# PDB_Custom_MCU.net
KiCad netlist of a schematic drawn in Altium Designer
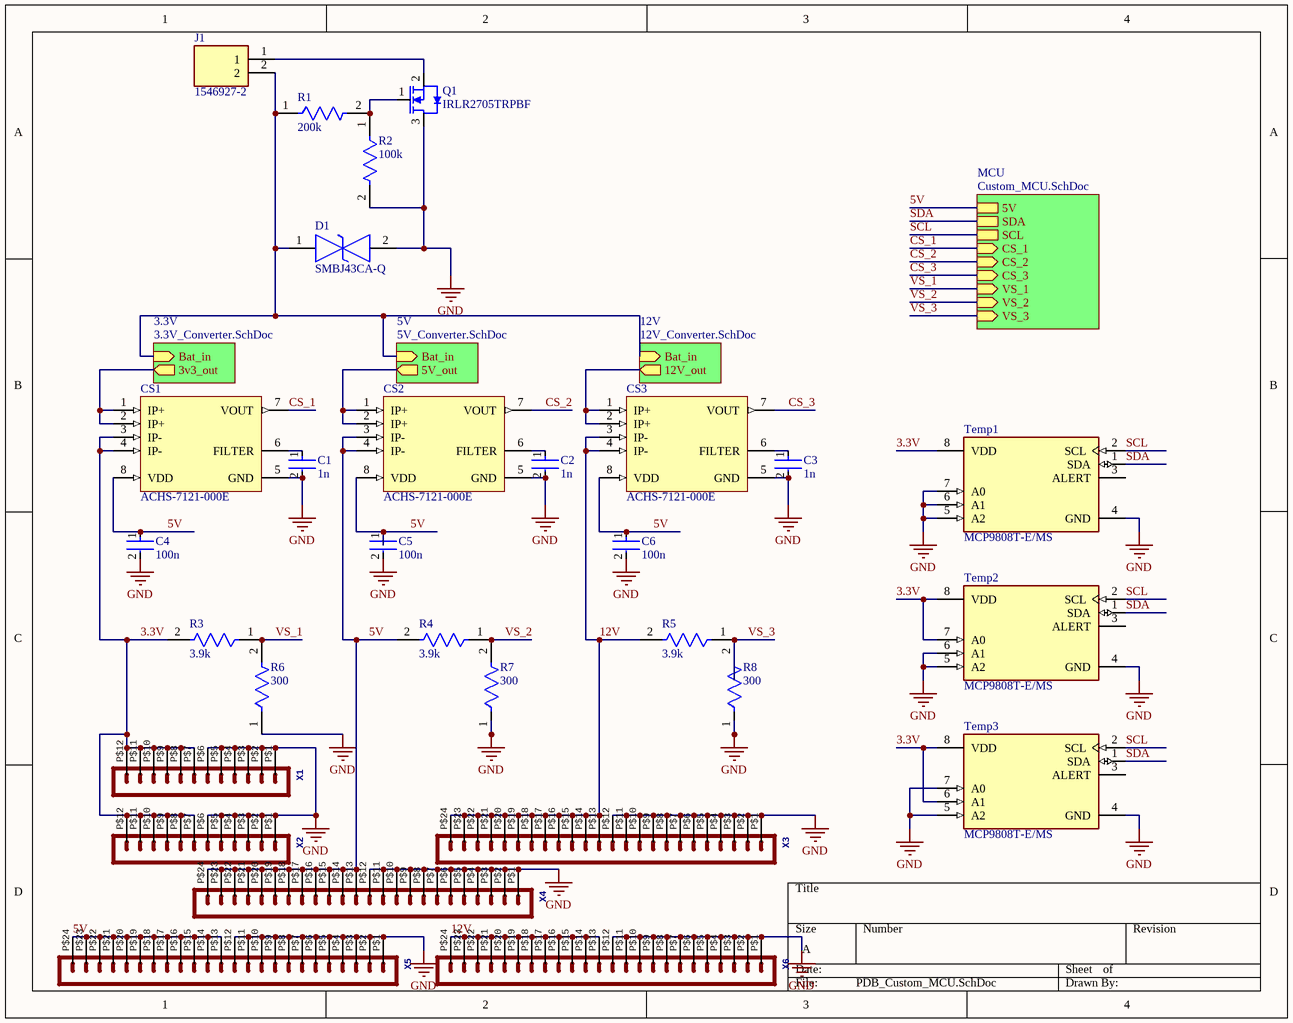
[diagram p0: PDB_Custom_MCU.SchDoc]

(export (version "E")
  (design (tool "Eeschema 10.0.6"))
  (components
    (comp (ref "C1")
      (value "1n")
      (footprint "FP-0603-L_1_6_0_15-W_0_81-IPC_A")
      (description "General Purpose Ceramic Capacitor, 0603, 1nF, 10%, X7R, 15%, 50V")
      (fields (field (name "VOLTAGE") "50V") (field (name "TOLERANCE") "10%"))
      (libsource (lib "Altium Content Vault") (part "02cd4be3c70576c341d710602a673aa"))
    )
    (comp (ref "C2")
      (value "1n")
      (footprint "FP-0603-L_1_6_0_15-W_0_81-IPC_A")
      (description "General Purpose Ceramic Capacitor, 0603, 1nF, 10%, X7R, 15%, 50V")
      (fields (field (name "VOLTAGE") "50V") (field (name "TOLERANCE") "10%"))
      (libsource (lib "Altium Content Vault") (part "02cd4be3c70576c341d710602a673aa"))
    )
    (comp (ref "C3")
      (value "1n")
      (footprint "FP-0603-L_1_6_0_15-W_0_81-IPC_A")
      (description "General Purpose Ceramic Capacitor, 0603, 1nF, 10%, X7R, 15%, 50V")
      (fields (field (name "VOLTAGE") "50V") (field (name "TOLERANCE") "10%"))
      (libsource (lib "Altium Content Vault") (part "02cd4be3c70576c341d710602a673aa"))
    )
    (comp (ref "C4")
      (value "100n")
      (footprint "FP-CGA3E-0_3-0_1-IPC_A")
      (description "Cap Ceramic 100nF 50V X7R 10% Pad SMD 0603 +125°C Automotive T/R")
      (fields (field (name "TOLERANCE") "10%") (field (name "VOLTAGE") "50V"))
      (libsource (lib "Altium Content Vault") (part "b4654b650e69147ec39a6b967a45e02"))
    )
    (comp (ref "C5")
      (value "100n")
      (footprint "FP-CGA3E-0_3-0_1-IPC_A")
      (description "Cap Ceramic 100nF 50V X7R 10% Pad SMD 0603 +125°C Automotive T/R")
      (fields (field (name "TOLERANCE") "10%") (field (name "VOLTAGE") "50V"))
      (libsource (lib "Altium Content Vault") (part "b4654b650e69147ec39a6b967a45e02"))
    )
    (comp (ref "C6")
      (value "100n")
      (footprint "FP-CGA3E-0_3-0_1-IPC_A")
      (description "Cap Ceramic 100nF 50V X7R 10% Pad SMD 0603 +125°C Automotive T/R")
      (fields (field (name "TOLERANCE") "10%") (field (name "VOLTAGE") "50V"))
      (libsource (lib "Altium Content Vault") (part "b4654b650e69147ec39a6b967a45e02"))
    )
    (comp (ref "CS1")
      (value "ACHS-7121-000E")
      (footprint "ACHS-7121-000E")
      (libsource (lib "ACHS-7121-000ECurrentSensor") (part "ACHS-7121-000E"))
    )
    (comp (ref "CS2")
      (value "ACHS-7121-000E")
      (footprint "ACHS-7121-000E")
      (libsource (lib "ACHS-7121-000ECurrentSensor") (part "ACHS-7121-000E"))
    )
    (comp (ref "CS3")
      (value "ACHS-7121-000E")
      (footprint "ACHS-7121-000E")
      (libsource (lib "ACHS-7121-000ECurrentSensor") (part "ACHS-7121-000E"))
    )
    (comp (ref "D1")
      (value "SMBJ43CA-Q")
      (footprint "SamacSys:DIONM5436X244N")
      (description "TVS Diode (Bi-directional)")
      (fields
        (field (name "MOUSER PART NUMBER") "652-SMBJ43CA-Q")
        (field (name "JLCPCB PART NUMBER") "C224021")
      )
      (libsource (lib "*") (part "SMBJ43CA-Q"))
    )
    (comp (ref "J1")
      (value "1546927-2")
      (footprint "SamacSys:SHDR2W119P0X826_1X2_1770X1549X1549P")
      (description "Connector")
      (fields (field (name "MOUSER PART NUMBER") "571-1546927-2"))
      (libsource (lib "*") (part "1546927-2"))
    )
    (comp (ref "Q1")
      (value "IRLR2705TRPBF")
      (footprint "IRLR2705TRPBF")
      (libsource (lib "Mosfetlib") (part "IRLR2705TRPBF"))
    )
    (comp (ref "R1")
      (value "200k")
      (footprint "FP-CRCW0603-e3-IPC_C")
      (description "RES Thick Film, 200kΩ, 1%, 0.1W, 100ppm/°C, 0603")
      (fields (field (name "TOLERANCE") "1%"))
      (libsource (lib "Altium Content Vault") (part "1029c3af85768c4190bb7ad29bc67b5"))
    )
    (comp (ref "R2")
      (value "100k")
      (footprint "FP-RC0603-0_55-MFG")
      (description "RES SMD 100K OHM 1% 1/10W 0603")
      (fields (field (name "TOLERANCE") "1%"))
      (libsource (lib "Altium Content Vault") (part "1029c3af85768c4190bb7ad29bc67b5"))
    )
    (comp (ref "R3")
      (value "3.9k")
      (footprint "FP-CRCW0603-e3-IPC_A")
      (description "RES Thick Film, 3.9kΩ, 1%, 0.1W, 100ppm/°C, 0603")
      (fields (field (name "TOLERANCE") "1%"))
      (libsource (lib "Altium Content Vault") (part "1029c3af85768c4190bb7ad29bc67b5"))
    )
    (comp (ref "R4")
      (value "3.9k")
      (footprint "FP-CRCW0603-e3-IPC_A")
      (description "RES Thick Film, 3.9kΩ, 1%, 0.1W, 100ppm/°C, 0603")
      (fields (field (name "TOLERANCE") "1%"))
      (libsource (lib "Altium Content Vault") (part "1029c3af85768c4190bb7ad29bc67b5"))
    )
    (comp (ref "R5")
      (value "3.9k")
      (footprint "FP-CRCW0603-e3-IPC_A")
      (description "RES Thick Film, 3.9kΩ, 1%, 0.1W, 100ppm/°C, 0603")
      (fields (field (name "TOLERANCE") "1%"))
      (libsource (lib "Altium Content Vault") (part "1029c3af85768c4190bb7ad29bc67b5"))
    )
    (comp (ref "R6")
      (value "300")
      (footprint "FP-CRCW0603-e3-IPC_A")
      (description "RES Thick Film, 300Ω, 1%, 0.1W, 100ppm/°C, 0603")
      (fields (field (name "TOLERANCE") "1%"))
      (libsource (lib "Altium Content Vault") (part "1029c3af85768c4190bb7ad29bc67b5"))
    )
    (comp (ref "R7")
      (value "300")
      (footprint "FP-CRCW0603-e3-IPC_A")
      (description "RES Thick Film, 300Ω, 1%, 0.1W, 100ppm/°C, 0603")
      (fields (field (name "TOLERANCE") "1%"))
      (libsource (lib "Altium Content Vault") (part "1029c3af85768c4190bb7ad29bc67b5"))
    )
    (comp (ref "R8")
      (value "300")
      (footprint "FP-CRCW0603-e3-IPC_A")
      (description "RES Thick Film, 300Ω, 1%, 0.1W, 100ppm/°C, 0603")
      (fields (field (name "TOLERANCE") "1%"))
      (libsource (lib "Altium Content Vault") (part "1029c3af85768c4190bb7ad29bc67b5"))
    )
    (comp (ref "Temp1")
      (value "MCP9808T-E/MS")
      (footprint "FP-C04-111-MFG")
      (description "SENSOR DIGITAL -40C-125C 8MSOP")
      (libsource (lib "Altium Content Vault") (part "a3d4f7632b752d27a24d286d1d70067"))
    )
    (comp (ref "Temp2")
      (value "MCP9808T-E/MS")
      (footprint "FP-C04-111-MFG")
      (description "SENSOR DIGITAL -40C-125C 8MSOP")
      (libsource (lib "Altium Content Vault") (part "a3d4f7632b752d27a24d286d1d70067"))
    )
    (comp (ref "Temp3")
      (value "MCP9808T-E/MS")
      (footprint "FP-C04-111-MFG")
      (description "SENSOR DIGITAL -40C-125C 8MSOP")
      (libsource (lib "Altium Content Vault") (part "a3d4f7632b752d27a24d286d1d70067"))
    )
    (comp (ref "X1")
      (value "Molex - Micro-Fit 3.0 Series connector,  3.00mm (0.118\") pitch header, 12 positions.")
      (footprint "44914-1201")
      (libsource (lib "Molex Microfit") (part "HEADER_POS12_?44914-1201"))
    )
    (comp (ref "X2")
      (value "Molex - Micro-Fit 3.0 Series connector,  3.00mm (0.118\") pitch header, 12 positions.")
      (footprint "44914-1201")
      (libsource (lib "Molex Microfit") (part "HEADER_POS12_?44914-1201"))
    )
    (comp (ref "X3")
      (value "Molex - Micro-Fit 3.0 Series connector,  3.00mm (0.118\") pitch header, 24 positions.")
      (footprint "44914-2401")
      (libsource (lib "Molex Microfit") (part "HEADER_POS24_?44914-2401"))
    )
    (comp (ref "X4")
      (value "Molex - Micro-Fit 3.0 Series connector,  3.00mm (0.118\") pitch header, 24 positions.")
      (footprint "44914-2401")
      (libsource (lib "Molex Microfit") (part "HEADER_POS24_?44914-2401"))
    )
    (comp (ref "X5")
      (value "Molex - Micro-Fit 3.0 Series connector,  3.00mm (0.118\") pitch header, 24 positions.")
      (footprint "44914-2401")
      (libsource (lib "Molex Microfit") (part "HEADER_POS24_?44914-2401"))
    )
    (comp (ref "X6")
      (value "Molex - Micro-Fit 3.0 Series connector,  3.00mm (0.118\") pitch header, 24 positions.")
      (footprint "44914-2401")
      (libsource (lib "Molex Microfit") (part "HEADER_POS24_?44914-2401"))
    )
  )
  (nets
    (net (code "1") (name "/3.3V") (class "Default")
      (node (ref "CS1") (pin "3") (pinfunction "IP-_3") (pintype "input"))
      (node (ref "CS1") (pin "4") (pinfunction "IP-_4") (pintype "input"))
      (node (ref "R3") (pin "2") (pinfunction "2_2") (pintype "passive"))
      (node (ref "Temp1") (pin "8") (pinfunction "VDD_8") (pintype "power_in"))
      (node (ref "Temp2") (pin "7") (pinfunction "A0_7") (pintype "input"))
      (node (ref "Temp2") (pin "8") (pinfunction "VDD_8") (pintype "power_in"))
      (node (ref "Temp3") (pin "6") (pinfunction "A1_6") (pintype "input"))
      (node (ref "Temp3") (pin "8") (pinfunction "VDD_8") (pintype "power_in"))
      (node (ref "X1") (pin "P$10") (pinfunction "10_P$10") (pintype "passive"))
      (node (ref "X1") (pin "P$11") (pinfunction "11_P$11") (pintype "passive"))
      (node (ref "X1") (pin "P$12") (pinfunction "12_P$12") (pintype "passive"))
      (node (ref "X1") (pin "P$7") (pinfunction "7_P$7") (pintype "passive"))
      (node (ref "X1") (pin "P$8") (pinfunction "8_P$8") (pintype "passive"))
      (node (ref "X1") (pin "P$9") (pinfunction "9_P$9") (pintype "passive"))
      (node (ref "X2") (pin "P$10") (pinfunction "10_P$10") (pintype "passive"))
      (node (ref "X2") (pin "P$11") (pinfunction "11_P$11") (pintype "passive"))
      (node (ref "X2") (pin "P$12") (pinfunction "12_P$12") (pintype "passive"))
      (node (ref "X2") (pin "P$7") (pinfunction "7_P$7") (pintype "passive"))
      (node (ref "X2") (pin "P$8") (pinfunction "8_P$8") (pintype "passive"))
      (node (ref "X2") (pin "P$9") (pinfunction "9_P$9") (pintype "passive"))
    )
    (net (code "2") (name "/3v3_out") (class "Default")
      (node (ref "CS1") (pin "1") (pinfunction "IP+_1") (pintype "input"))
      (node (ref "CS1") (pin "2") (pinfunction "IP+_2") (pintype "input"))
    )
    (net (code "3") (name "/5V") (class "Default")
      (node (ref "C4") (pin "1") (pinfunction "1_1") (pintype "passive"))
      (node (ref "C5") (pin "1") (pinfunction "1_1") (pintype "passive"))
      (node (ref "C6") (pin "1") (pinfunction "1_1") (pintype "passive"))
      (node (ref "CS1") (pin "8") (pinfunction "VDD_8") (pintype "input"))
      (node (ref "CS2") (pin "3") (pinfunction "IP-_3") (pintype "input"))
      (node (ref "CS2") (pin "4") (pinfunction "IP-_4") (pintype "input"))
      (node (ref "CS2") (pin "8") (pinfunction "VDD_8") (pintype "input"))
      (node (ref "CS3") (pin "8") (pinfunction "VDD_8") (pintype "input"))
      (node (ref "R4") (pin "2") (pinfunction "2_2") (pintype "passive"))
      (node (ref "X4") (pin "P$13") (pinfunction "13_P$13") (pintype "passive"))
      (node (ref "X4") (pin "P$14") (pinfunction "14_P$14") (pintype "passive"))
      (node (ref "X4") (pin "P$15") (pinfunction "15_P$15") (pintype "passive"))
      (node (ref "X4") (pin "P$16") (pinfunction "16_P$16") (pintype "passive"))
      (node (ref "X4") (pin "P$17") (pinfunction "17_P$17") (pintype "passive"))
      (node (ref "X4") (pin "P$18") (pinfunction "18_P$18") (pintype "passive"))
      (node (ref "X4") (pin "P$19") (pinfunction "19_P$19") (pintype "passive"))
      (node (ref "X4") (pin "P$20") (pinfunction "20_P$20") (pintype "passive"))
      (node (ref "X4") (pin "P$21") (pinfunction "21_P$21") (pintype "passive"))
      (node (ref "X4") (pin "P$22") (pinfunction "22_P$22") (pintype "passive"))
      (node (ref "X4") (pin "P$23") (pinfunction "23_P$23") (pintype "passive"))
      (node (ref "X4") (pin "P$24") (pinfunction "24_P$24") (pintype "passive"))
      (node (ref "X5") (pin "P$13") (pinfunction "13_P$13") (pintype "passive"))
      (node (ref "X5") (pin "P$14") (pinfunction "14_P$14") (pintype "passive"))
      (node (ref "X5") (pin "P$15") (pinfunction "15_P$15") (pintype "passive"))
      (node (ref "X5") (pin "P$16") (pinfunction "16_P$16") (pintype "passive"))
      (node (ref "X5") (pin "P$17") (pinfunction "17_P$17") (pintype "passive"))
      (node (ref "X5") (pin "P$18") (pinfunction "18_P$18") (pintype "passive"))
      (node (ref "X5") (pin "P$19") (pinfunction "19_P$19") (pintype "passive"))
      (node (ref "X5") (pin "P$20") (pinfunction "20_P$20") (pintype "passive"))
      (node (ref "X5") (pin "P$21") (pinfunction "21_P$21") (pintype "passive"))
      (node (ref "X5") (pin "P$22") (pinfunction "22_P$22") (pintype "passive"))
      (node (ref "X5") (pin "P$23") (pinfunction "23_P$23") (pintype "passive"))
      (node (ref "X5") (pin "P$24") (pinfunction "24_P$24") (pintype "passive"))
    )
    (net (code "4") (name "/5V_out") (class "Default")
      (node (ref "CS2") (pin "1") (pinfunction "IP+_1") (pintype "input"))
      (node (ref "CS2") (pin "2") (pinfunction "IP+_2") (pintype "input"))
    )
    (net (code "5") (name "/12V") (class "Default")
      (node (ref "CS3") (pin "3") (pinfunction "IP-_3") (pintype "input"))
      (node (ref "CS3") (pin "4") (pinfunction "IP-_4") (pintype "input"))
      (node (ref "R5") (pin "2") (pinfunction "2_2") (pintype "passive"))
      (node (ref "X3") (pin "P$13") (pinfunction "13_P$13") (pintype "passive"))
      (node (ref "X3") (pin "P$14") (pinfunction "14_P$14") (pintype "passive"))
      (node (ref "X3") (pin "P$15") (pinfunction "15_P$15") (pintype "passive"))
      (node (ref "X3") (pin "P$16") (pinfunction "16_P$16") (pintype "passive"))
      (node (ref "X3") (pin "P$17") (pinfunction "17_P$17") (pintype "passive"))
      (node (ref "X3") (pin "P$18") (pinfunction "18_P$18") (pintype "passive"))
      (node (ref "X3") (pin "P$19") (pinfunction "19_P$19") (pintype "passive"))
      (node (ref "X3") (pin "P$20") (pinfunction "20_P$20") (pintype "passive"))
      (node (ref "X3") (pin "P$21") (pinfunction "21_P$21") (pintype "passive"))
      (node (ref "X3") (pin "P$22") (pinfunction "22_P$22") (pintype "passive"))
      (node (ref "X3") (pin "P$23") (pinfunction "23_P$23") (pintype "passive"))
      (node (ref "X3") (pin "P$24") (pinfunction "24_P$24") (pintype "passive"))
      (node (ref "X6") (pin "P$13") (pinfunction "13_P$13") (pintype "passive"))
      (node (ref "X6") (pin "P$14") (pinfunction "14_P$14") (pintype "passive"))
      (node (ref "X6") (pin "P$15") (pinfunction "15_P$15") (pintype "passive"))
      (node (ref "X6") (pin "P$16") (pinfunction "16_P$16") (pintype "passive"))
      (node (ref "X6") (pin "P$17") (pinfunction "17_P$17") (pintype "passive"))
      (node (ref "X6") (pin "P$18") (pinfunction "18_P$18") (pintype "passive"))
      (node (ref "X6") (pin "P$19") (pinfunction "19_P$19") (pintype "passive"))
      (node (ref "X6") (pin "P$20") (pinfunction "20_P$20") (pintype "passive"))
      (node (ref "X6") (pin "P$21") (pinfunction "21_P$21") (pintype "passive"))
      (node (ref "X6") (pin "P$22") (pinfunction "22_P$22") (pintype "passive"))
      (node (ref "X6") (pin "P$23") (pinfunction "23_P$23") (pintype "passive"))
      (node (ref "X6") (pin "P$24") (pinfunction "24_P$24") (pintype "passive"))
    )
    (net (code "6") (name "/12V_out") (class "Default")
      (node (ref "CS3") (pin "1") (pinfunction "IP+_1") (pintype "input"))
      (node (ref "CS3") (pin "2") (pinfunction "IP+_2") (pintype "input"))
    )
    (net (code "7") (name "/Bat_in") (class "Default")
      (node (ref "D1") (pin "1") (pinfunction "1_1") (pintype "passive"))
      (node (ref "J1") (pin "2") (pinfunction "2_2") (pintype "passive"))
      (node (ref "R1") (pin "1") (pinfunction "1_1") (pintype "passive"))
    )
    (net (code "8") (name "/CS_1") (class "Default")
      (node (ref "CS1") (pin "7") (pinfunction "VOUT_7") (pintype "output"))
    )
    (net (code "9") (name "/CS_2") (class "Default")
      (node (ref "CS2") (pin "7") (pinfunction "VOUT_7") (pintype "output"))
    )
    (net (code "10") (name "/CS_3") (class "Default")
      (node (ref "CS3") (pin "7") (pinfunction "VOUT_7") (pintype "output"))
    )
    (net (code "11") (name "/SCL") (class "Default")
      (node (ref "Temp1") (pin "2") (pinfunction "SCL_2") (pintype "input"))
      (node (ref "Temp2") (pin "2") (pinfunction "SCL_2") (pintype "input"))
      (node (ref "Temp3") (pin "2") (pinfunction "SCL_2") (pintype "input"))
    )
    (net (code "12") (name "/SDA") (class "Default")
      (node (ref "Temp1") (pin "1") (pinfunction "SDA_1") (pintype "bidirectional"))
      (node (ref "Temp2") (pin "1") (pinfunction "SDA_1") (pintype "bidirectional"))
      (node (ref "Temp3") (pin "1") (pinfunction "SDA_1") (pintype "bidirectional"))
    )
    (net (code "13") (name "/VS_1") (class "Default")
      (node (ref "R3") (pin "1") (pinfunction "1_1") (pintype "passive"))
      (node (ref "R6") (pin "2") (pinfunction "2_2") (pintype "passive"))
    )
    (net (code "14") (name "/VS_2") (class "Default")
      (node (ref "R4") (pin "1") (pinfunction "1_1") (pintype "passive"))
      (node (ref "R7") (pin "2") (pinfunction "2_2") (pintype "passive"))
    )
    (net (code "15") (name "/VS_3") (class "Default")
      (node (ref "R5") (pin "1") (pinfunction "1_1") (pintype "passive"))
      (node (ref "R8") (pin "2") (pinfunction "2_2") (pintype "passive"))
    )
    (net (code "16") (name "GND") (class "Default")
      (node (ref "C1") (pin "2") (pinfunction "2_2") (pintype "passive"))
      (node (ref "C2") (pin "2") (pinfunction "2_2") (pintype "passive"))
      (node (ref "C3") (pin "2") (pinfunction "2_2") (pintype "passive"))
      (node (ref "C4") (pin "2") (pinfunction "2_2") (pintype "passive"))
      (node (ref "C5") (pin "2") (pinfunction "2_2") (pintype "passive"))
      (node (ref "C6") (pin "2") (pinfunction "2_2") (pintype "passive"))
      (node (ref "CS1") (pin "5") (pinfunction "GND_5") (pintype "passive"))
      (node (ref "CS2") (pin "5") (pinfunction "GND_5") (pintype "passive"))
      (node (ref "CS3") (pin "5") (pinfunction "GND_5") (pintype "passive"))
      (node (ref "D1") (pin "2") (pinfunction "2_2") (pintype "passive"))
      (node (ref "Q1") (pin "3") (pinfunction "3_3") (pintype "passive"))
      (node (ref "R2") (pin "2") (pinfunction "2_2") (pintype "passive"))
      (node (ref "R6") (pin "1") (pinfunction "1_1") (pintype "passive"))
      (node (ref "R7") (pin "1") (pinfunction "1_1") (pintype "passive"))
      (node (ref "R8") (pin "1") (pinfunction "1_1") (pintype "passive"))
      (node (ref "Temp1") (pin "4") (pinfunction "GND_4") (pintype "power_in"))
      (node (ref "Temp1") (pin "5") (pinfunction "A2_5") (pintype "input"))
      (node (ref "Temp1") (pin "6") (pinfunction "A1_6") (pintype "input"))
      (node (ref "Temp1") (pin "7") (pinfunction "A0_7") (pintype "input"))
      (node (ref "Temp2") (pin "4") (pinfunction "GND_4") (pintype "power_in"))
      (node (ref "Temp2") (pin "5") (pinfunction "A2_5") (pintype "input"))
      (node (ref "Temp2") (pin "6") (pinfunction "A1_6") (pintype "input"))
      (node (ref "Temp3") (pin "4") (pinfunction "GND_4") (pintype "power_in"))
      (node (ref "Temp3") (pin "5") (pinfunction "A2_5") (pintype "input"))
      (node (ref "Temp3") (pin "7") (pinfunction "A0_7") (pintype "input"))
      (node (ref "X1") (pin "P$1") (pinfunction "1_P$1") (pintype "passive"))
      (node (ref "X1") (pin "P$2") (pinfunction "2_P$2") (pintype "passive"))
      (node (ref "X1") (pin "P$3") (pinfunction "3_P$3") (pintype "passive"))
      (node (ref "X1") (pin "P$4") (pinfunction "4_P$4") (pintype "passive"))
      (node (ref "X1") (pin "P$5") (pinfunction "5_P$5") (pintype "passive"))
      (node (ref "X1") (pin "P$6") (pinfunction "6_P$6") (pintype "passive"))
      (node (ref "X2") (pin "P$1") (pinfunction "1_P$1") (pintype "passive"))
      (node (ref "X2") (pin "P$2") (pinfunction "2_P$2") (pintype "passive"))
      (node (ref "X2") (pin "P$3") (pinfunction "3_P$3") (pintype "passive"))
      (node (ref "X2") (pin "P$4") (pinfunction "4_P$4") (pintype "passive"))
      (node (ref "X2") (pin "P$5") (pinfunction "5_P$5") (pintype "passive"))
      (node (ref "X2") (pin "P$6") (pinfunction "6_P$6") (pintype "passive"))
      (node (ref "X3") (pin "P$1") (pinfunction "1_P$1") (pintype "passive"))
      (node (ref "X3") (pin "P$10") (pinfunction "10_P$10") (pintype "passive"))
      (node (ref "X3") (pin "P$11") (pinfunction "11_P$11") (pintype "passive"))
      (node (ref "X3") (pin "P$12") (pinfunction "12_P$12") (pintype "passive"))
      (node (ref "X3") (pin "P$2") (pinfunction "2_P$2") (pintype "passive"))
      (node (ref "X3") (pin "P$3") (pinfunction "3_P$3") (pintype "passive"))
      (node (ref "X3") (pin "P$4") (pinfunction "4_P$4") (pintype "passive"))
      (node (ref "X3") (pin "P$5") (pinfunction "5_P$5") (pintype "passive"))
      (node (ref "X3") (pin "P$6") (pinfunction "6_P$6") (pintype "passive"))
      (node (ref "X3") (pin "P$7") (pinfunction "7_P$7") (pintype "passive"))
      (node (ref "X3") (pin "P$8") (pinfunction "8_P$8") (pintype "passive"))
      (node (ref "X3") (pin "P$9") (pinfunction "9_P$9") (pintype "passive"))
      (node (ref "X4") (pin "P$1") (pinfunction "1_P$1") (pintype "passive"))
      (node (ref "X4") (pin "P$10") (pinfunction "10_P$10") (pintype "passive"))
      (node (ref "X4") (pin "P$11") (pinfunction "11_P$11") (pintype "passive"))
      (node (ref "X4") (pin "P$12") (pinfunction "12_P$12") (pintype "passive"))
      (node (ref "X4") (pin "P$2") (pinfunction "2_P$2") (pintype "passive"))
      (node (ref "X4") (pin "P$3") (pinfunction "3_P$3") (pintype "passive"))
      (node (ref "X4") (pin "P$4") (pinfunction "4_P$4") (pintype "passive"))
      (node (ref "X4") (pin "P$5") (pinfunction "5_P$5") (pintype "passive"))
      (node (ref "X4") (pin "P$6") (pinfunction "6_P$6") (pintype "passive"))
      (node (ref "X4") (pin "P$7") (pinfunction "7_P$7") (pintype "passive"))
      (node (ref "X4") (pin "P$8") (pinfunction "8_P$8") (pintype "passive"))
      (node (ref "X4") (pin "P$9") (pinfunction "9_P$9") (pintype "passive"))
      (node (ref "X5") (pin "P$1") (pinfunction "1_P$1") (pintype "passive"))
      (node (ref "X5") (pin "P$10") (pinfunction "10_P$10") (pintype "passive"))
      (node (ref "X5") (pin "P$11") (pinfunction "11_P$11") (pintype "passive"))
      (node (ref "X5") (pin "P$12") (pinfunction "12_P$12") (pintype "passive"))
      (node (ref "X5") (pin "P$2") (pinfunction "2_P$2") (pintype "passive"))
      (node (ref "X5") (pin "P$3") (pinfunction "3_P$3") (pintype "passive"))
      (node (ref "X5") (pin "P$4") (pinfunction "4_P$4") (pintype "passive"))
      (node (ref "X5") (pin "P$5") (pinfunction "5_P$5") (pintype "passive"))
      (node (ref "X5") (pin "P$6") (pinfunction "6_P$6") (pintype "passive"))
      (node (ref "X5") (pin "P$7") (pinfunction "7_P$7") (pintype "passive"))
      (node (ref "X5") (pin "P$8") (pinfunction "8_P$8") (pintype "passive"))
      (node (ref "X5") (pin "P$9") (pinfunction "9_P$9") (pintype "passive"))
      (node (ref "X6") (pin "P$1") (pinfunction "1_P$1") (pintype "passive"))
      (node (ref "X6") (pin "P$10") (pinfunction "10_P$10") (pintype "passive"))
      (node (ref "X6") (pin "P$11") (pinfunction "11_P$11") (pintype "passive"))
      (node (ref "X6") (pin "P$12") (pinfunction "12_P$12") (pintype "passive"))
      (node (ref "X6") (pin "P$2") (pinfunction "2_P$2") (pintype "passive"))
      (node (ref "X6") (pin "P$3") (pinfunction "3_P$3") (pintype "passive"))
      (node (ref "X6") (pin "P$4") (pinfunction "4_P$4") (pintype "passive"))
      (node (ref "X6") (pin "P$5") (pinfunction "5_P$5") (pintype "passive"))
      (node (ref "X6") (pin "P$6") (pinfunction "6_P$6") (pintype "passive"))
      (node (ref "X6") (pin "P$7") (pinfunction "7_P$7") (pintype "passive"))
      (node (ref "X6") (pin "P$8") (pinfunction "8_P$8") (pintype "passive"))
      (node (ref "X6") (pin "P$9") (pinfunction "9_P$9") (pintype "passive"))
    )
    (net (code "17") (name "Net-(CS1-FILTER)") (class "Default")
      (node (ref "C1") (pin "1") (pinfunction "1_1") (pintype "passive"))
      (node (ref "CS1") (pin "6") (pinfunction "FILTER_6") (pintype "passive"))
    )
    (net (code "18") (name "Net-(CS2-FILTER)") (class "Default")
      (node (ref "C2") (pin "1") (pinfunction "1_1") (pintype "passive"))
      (node (ref "CS2") (pin "6") (pinfunction "FILTER_6") (pintype "passive"))
    )
    (net (code "19") (name "Net-(CS3-FILTER)") (class "Default")
      (node (ref "C3") (pin "1") (pinfunction "1_1") (pintype "passive"))
      (node (ref "CS3") (pin "6") (pinfunction "FILTER_6") (pintype "passive"))
    )
    (net (code "20") (name "Net-(J1-Pad1)") (class "Default")
      (node (ref "J1") (pin "1") (pinfunction "1_1") (pintype "passive"))
      (node (ref "Q1") (pin "2") (pinfunction "2_2") (pintype "passive"))
    )
    (net (code "21") (name "Net-(Q1-Pad1)") (class "Default")
      (node (ref "Q1") (pin "1") (pinfunction "1_1") (pintype "passive"))
      (node (ref "R1") (pin "2") (pinfunction "2_2") (pintype "passive"))
      (node (ref "R2") (pin "1") (pinfunction "1_1") (pintype "passive"))
    )
    (net (code "22") (name "unconnected-(Temp1-ALERT-Pad3)") (class "Default")
      (node (ref "Temp1") (pin "3") (pinfunction "ALERT_3") (pintype "open_collector"))
    )
    (net (code "23") (name "unconnected-(Temp2-ALERT-Pad3)") (class "Default")
      (node (ref "Temp2") (pin "3") (pinfunction "ALERT_3") (pintype "open_collector"))
    )
    (net (code "24") (name "unconnected-(Temp3-ALERT-Pad3)") (class "Default")
      (node (ref "Temp3") (pin "3") (pinfunction "ALERT_3") (pintype "open_collector"))
    )
  )
)
